# Battery_Monitoring_with_kill_Schematic.net
KiCad netlist of a schematic drawn in EAGLE
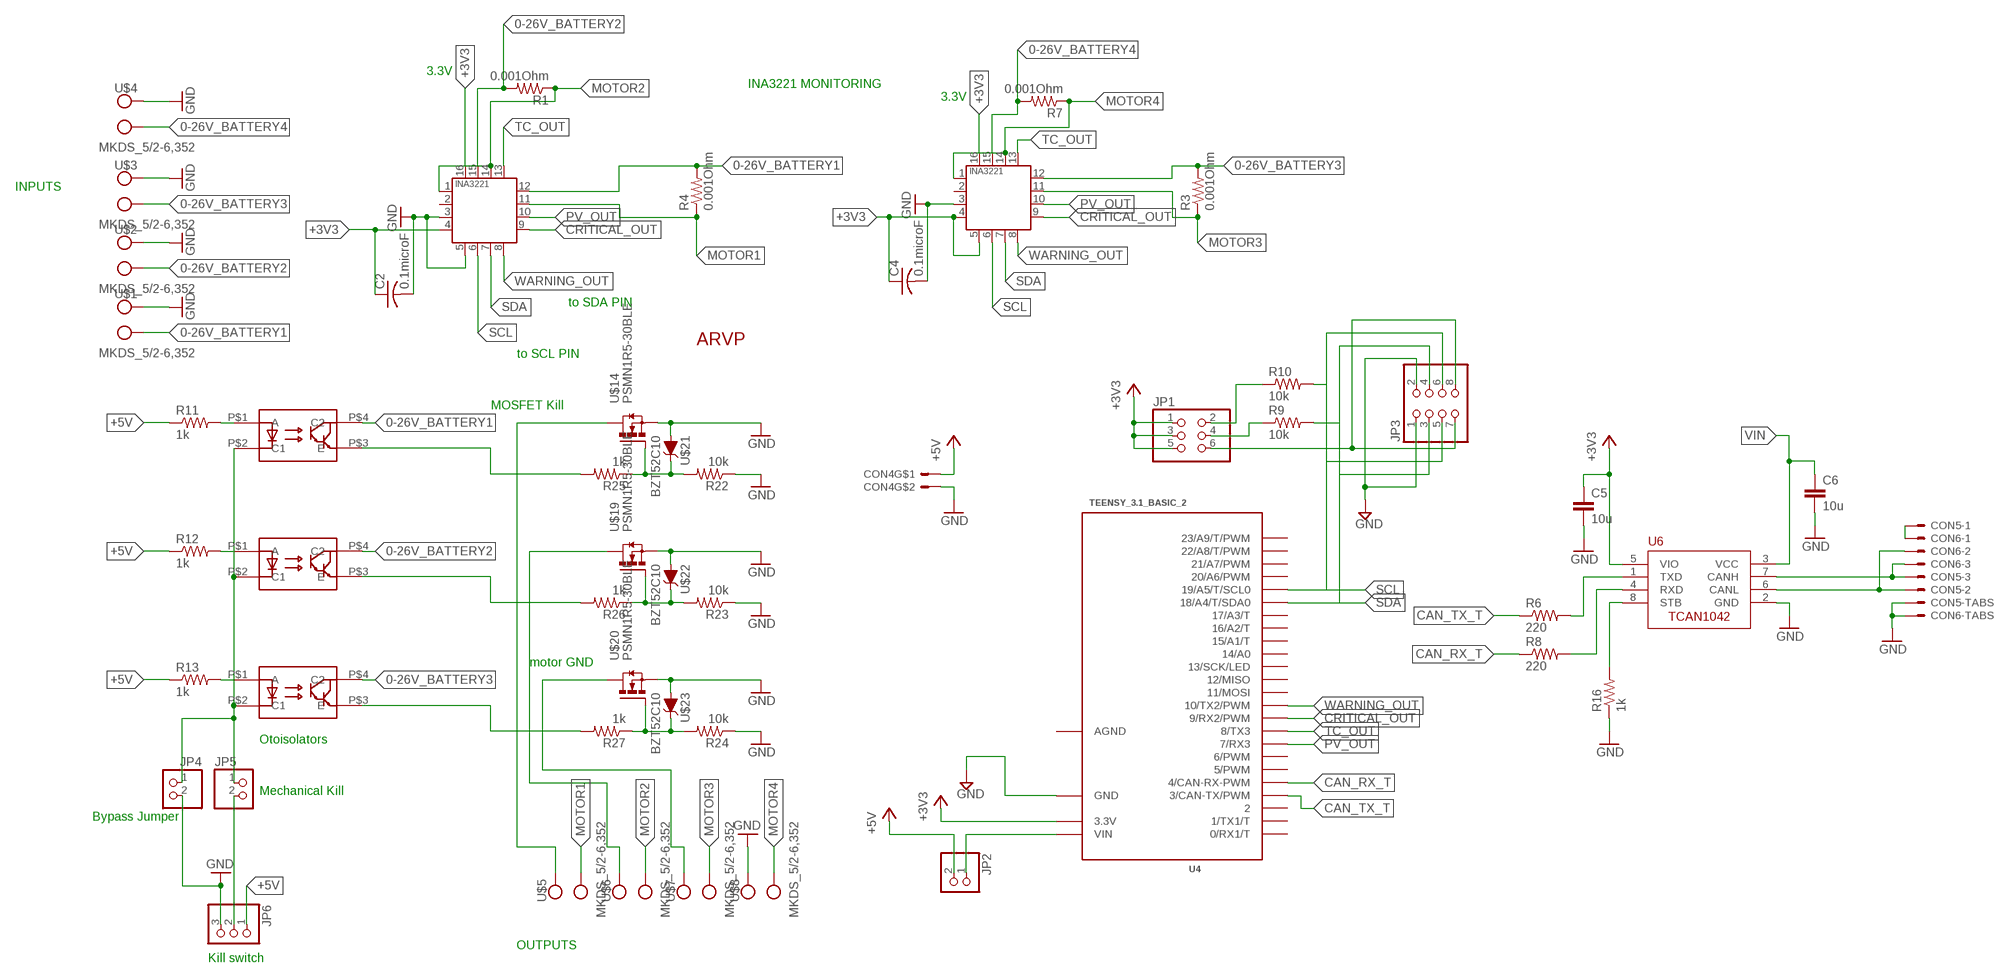
[diagram p0: schematic, sheet 1]

(export (version "E")
  (design (tool "Eeschema 10.0.6"))
  (components
    (comp (ref "C2")
      (value "0.1microF")
      (footprint "eagle-import:C2012")
      (libsource (lib "eagle-import") (part "C-USC2012"))
    )
    (comp (ref "C4")
      (value "0.1microF")
      (footprint "eagle-import:C2012")
      (libsource (lib "eagle-import") (part "C-USC2012"))
    )
    (comp (ref "C5")
      (value "10u")
      (footprint "eagle-import:C0805")
      (libsource (lib "eagle-import") (part "C-EUC0805"))
    )
    (comp (ref "C6")
      (value "10u")
      (footprint "eagle-import:C0805")
      (libsource (lib "eagle-import") (part "C-EUC0805"))
    )
    (comp (ref "CON4")
      (value "MOLEX_5566-2")
      (footprint "eagle-import:5566-2")
      (libsource (lib "eagle-import") (part "MOLEX_5566-2"))
    )
    (comp (ref "CON5")
      (value "S3B-PH-SM4-TB")
      (footprint "eagle-import:S3B-PH-SM4-TB")
      (libsource (lib "eagle-import") (part "S3B-PH-SM4-TB"))
    )
    (comp (ref "CON6")
      (value "S3B-PH-SM4-TB")
      (footprint "eagle-import:S3B-PH-SM4-TB")
      (libsource (lib "eagle-import") (part "S3B-PH-SM4-TB"))
    )
    (comp (ref "JP1")
      (value "PINHD-2X3")
      (footprint "eagle-import:2X03")
      (libsource (lib "eagle-import") (part "PINHD-2X3"))
    )
    (comp (ref "JP2")
      (value "PINHD-1X2")
      (footprint "eagle-import:1X02")
      (libsource (lib "eagle-import") (part "PINHD-1X2"))
    )
    (comp (ref "JP3")
      (value "PINHD-2X4")
      (footprint "eagle-import:2X04")
      (libsource (lib "eagle-import") (part "PINHD-2X4"))
    )
    (comp (ref "JP4")
      (value "PINHD-1X2")
      (footprint "eagle-import:1X02")
      (libsource (lib "eagle-import") (part "PINHD-1X2"))
    )
    (comp (ref "JP5")
      (value "PINHD-1X2")
      (footprint "eagle-import:1X02")
      (libsource (lib "eagle-import") (part "PINHD-1X2"))
    )
    (comp (ref "JP6")
      (value "PINHD-1X3")
      (footprint "eagle-import:1X03")
      (libsource (lib "eagle-import") (part "PINHD-1X3"))
    )
    (comp (ref "R1")
      (value "0.001Ohm")
      (footprint "eagle-import:3920")
      (libsource (lib "eagle-import") (part "HCS3920FT1L00"))
    )
    (comp (ref "R3")
      (value "0.001Ohm")
      (footprint "eagle-import:3920")
      (libsource (lib "eagle-import") (part "HCS3920FT1L00"))
    )
    (comp (ref "R4")
      (value "0.001Ohm")
      (footprint "eagle-import:3920")
      (libsource (lib "eagle-import") (part "HCS3920FT1L00"))
    )
    (comp (ref "R6")
      (value "220")
      (footprint "eagle-import:R0805")
      (libsource (lib "eagle-import") (part "rcl_334_R-US_R0805"))
    )
    (comp (ref "R7")
      (value "0.001Ohm")
      (footprint "eagle-import:3920")
      (libsource (lib "eagle-import") (part "HCS3920FT1L00"))
    )
    (comp (ref "R8")
      (value "220")
      (footprint "eagle-import:R0805")
      (libsource (lib "eagle-import") (part "rcl_334_R-US_R0805"))
    )
    (comp (ref "R9")
      (value "10k")
      (footprint "eagle-import:R1206")
      (libsource (lib "eagle-import") (part "rcl_334_R-US_R1206"))
    )
    (comp (ref "R10")
      (value "10k")
      (footprint "eagle-import:R1206")
      (libsource (lib "eagle-import") (part "rcl_334_R-US_R1206"))
    )
    (comp (ref "R11")
      (value "1k")
      (footprint "eagle-import:R0805")
      (libsource (lib "eagle-import") (part "R-US_R0805"))
    )
    (comp (ref "R12")
      (value "1k")
      (footprint "eagle-import:R0805")
      (libsource (lib "eagle-import") (part "R-US_R0805"))
    )
    (comp (ref "R13")
      (value "1k")
      (footprint "eagle-import:R0805")
      (libsource (lib "eagle-import") (part "R-US_R0805"))
    )
    (comp (ref "R16")
      (value "1k")
      (footprint "eagle-import:R0805")
      (libsource (lib "eagle-import") (part "rcl_334_R-US_R0805"))
    )
    (comp (ref "R22")
      (value "10k")
      (footprint "eagle-import:M1206")
      (libsource (lib "eagle-import") (part "R-US_M1206"))
    )
    (comp (ref "R23")
      (value "10k")
      (footprint "eagle-import:M1206")
      (libsource (lib "eagle-import") (part "R-US_M1206"))
    )
    (comp (ref "R24")
      (value "10k")
      (footprint "eagle-import:M1206")
      (libsource (lib "eagle-import") (part "R-US_M1206"))
    )
    (comp (ref "R25")
      (value "1k")
      (footprint "eagle-import:M1206")
      (libsource (lib "eagle-import") (part "R-US_M1206"))
    )
    (comp (ref "R26")
      (value "1k")
      (footprint "eagle-import:M1206")
      (libsource (lib "eagle-import") (part "R-US_M1206"))
    )
    (comp (ref "R27")
      (value "1k")
      (footprint "eagle-import:M1206")
      (libsource (lib "eagle-import") (part "R-US_M1206"))
    )
    (comp (ref "U$1")
      (value "MKDS_5/2-6,352")
      (footprint "eagle-import:MKDS_5_2-6,35")
      (libsource (lib "eagle-import") (part "MKDS_5/2-6,352"))
    )
    (comp (ref "U$2")
      (value "MKDS_5/2-6,352")
      (footprint "eagle-import:MKDS_5_2-6,35")
      (libsource (lib "eagle-import") (part "MKDS_5/2-6,352"))
    )
    (comp (ref "U$3")
      (value "MKDS_5/2-6,352")
      (footprint "eagle-import:MKDS_5_2-6,35")
      (libsource (lib "eagle-import") (part "MKDS_5/2-6,352"))
    )
    (comp (ref "U$4")
      (value "MKDS_5/2-6,352")
      (footprint "eagle-import:MKDS_5_2-6,35")
      (libsource (lib "eagle-import") (part "MKDS_5/2-6,352"))
    )
    (comp (ref "U$5")
      (value "MKDS_5/2-6,352")
      (footprint "eagle-import:MKDS_5_2-6,35")
      (libsource (lib "eagle-import") (part "MKDS_5/2-6,352"))
    )
    (comp (ref "U$6")
      (value "MKDS_5/2-6,352")
      (footprint "eagle-import:MKDS_5_2-6,35")
      (libsource (lib "eagle-import") (part "MKDS_5/2-6,352"))
    )
    (comp (ref "U$7")
      (value "MKDS_5/2-6,352")
      (footprint "eagle-import:MKDS_5_2-6,35")
      (libsource (lib "eagle-import") (part "MKDS_5/2-6,352"))
    )
    (comp (ref "U$8")
      (value "MKDS_5/2-6,352")
      (footprint "eagle-import:MKDS_5_2-6,35")
      (libsource (lib "eagle-import") (part "MKDS_5/2-6,352"))
    )
    (comp (ref "U$10")
      (value "ARVP_LOGO")
      (footprint "eagle-import:ARVP")
      (libsource (lib "eagle-import") (part "ARVP_LOGO"))
    )
    (comp (ref "U$11")
      (value "TCLD1000CT")
      (footprint "eagle-import:SOP-4L")
      (fields (field (name "SPICEPREFIX") "E"))
      (libsource (lib "eagle-import") (part "TCLD1000CT"))
    )
    (comp (ref "U$12")
      (value "TCLD1000CT")
      (footprint "eagle-import:SOP-4L")
      (libsource (lib "eagle-import") (part "TCLD1000CT"))
    )
    (comp (ref "U$13")
      (value "TCLD1000CT")
      (footprint "eagle-import:SOP-4L")
      (libsource (lib "eagle-import") (part "TCLD1000CT"))
    )
    (comp (ref "U$14")
      (value "PSMN1R5-30BLE")
      (footprint "eagle-import:SOT404_D2PAK")
      (libsource (lib "eagle-import") (part "PSMN1R5-30BLE"))
    )
    (comp (ref "U$19")
      (value "PSMN1R5-30BLE")
      (footprint "eagle-import:SOT404_D2PAK")
      (libsource (lib "eagle-import") (part "PSMN1R5-30BLE"))
    )
    (comp (ref "U$20")
      (value "PSMN1R5-30BLE")
      (footprint "eagle-import:SOT404_D2PAK")
      (libsource (lib "eagle-import") (part "PSMN1R5-30BLE"))
    )
    (comp (ref "U$21")
      (value "BZT52C10")
      (footprint "eagle-import:SOD-123")
      (libsource (lib "eagle-import") (part "BZT52C10"))
    )
    (comp (ref "U$22")
      (value "BZT52C10")
      (footprint "eagle-import:SOD-123")
      (libsource (lib "eagle-import") (part "BZT52C10"))
    )
    (comp (ref "U$23")
      (value "BZT52C10")
      (footprint "eagle-import:SOD-123")
      (libsource (lib "eagle-import") (part "BZT52C10"))
    )
    (comp (ref "U1")
      (value "INA3221.")
      (footprint "eagle-import:HVQFN16_4X4")
      (libsource (lib "eagle-import") (part "INA3221."))
    )
    (comp (ref "U2")
      (value "INA3221.")
      (footprint "eagle-import:HVQFN16_4X4")
      (libsource (lib "eagle-import") (part "INA3221."))
    )
    (comp (ref "U4")
      (value "TEENSY_3.1_BASIC_2")
      (footprint "eagle-import:TEENSY_3.1_BASIC_2")
      (libsource (lib "eagle-import") (part "TEENSY_3.1_BASIC_2"))
    )
    (comp (ref "U6")
      (value "TCAN1042HVDR")
      (footprint "eagle-import:SO-8")
      (libsource (lib "eagle-import") (part "TCAN1042HVDR"))
    )
  )
  (nets
    (net (code "1") (name "+3V3") (class "Default")
      (node (ref "C2") (pin "1") (pinfunction "1_1") (pintype "passive"))
      (node (ref "C4") (pin "1") (pinfunction "1_1") (pintype "passive"))
      (node (ref "C5") (pin "1") (pinfunction "1_1") (pintype "passive"))
      (node (ref "JP1") (pin "1") (pinfunction "1_1") (pintype "passive"))
      (node (ref "JP1") (pin "3") (pinfunction "3_3") (pintype "passive"))
      (node (ref "JP1") (pin "5") (pinfunction "5_5") (pintype "passive"))
      (node (ref "U1") (pin "16") (pinfunction "VPU_16") (pintype "input"))
      (node (ref "U1") (pin "4") (pinfunction "VS_4") (pintype "power_in"))
      (node (ref "U2") (pin "16") (pinfunction "VPU_16") (pintype "input"))
      (node (ref "U2") (pin "4") (pinfunction "VS_4") (pintype "power_in"))
      (node (ref "U2") (pin "5") (pinfunction "A0_5") (pintype "input"))
      (node (ref "U4") (pin "3.3V") (pinfunction "3.3V_3.3V") (pintype "power_in"))
      (node (ref "U6") (pin "5") (pinfunction "VIO_5") (pintype "bidirectional"))
    )
    (net (code "2") (name "+5V") (class "Default")
      (node (ref "CON4") (pin "1") (pinfunction "S_1") (pintype "passive"))
      (node (ref "JP2") (pin "2") (pinfunction "2_2") (pintype "passive"))
      (node (ref "JP6") (pin "1") (pinfunction "1_1") (pintype "passive"))
      (node (ref "R11") (pin "1") (pinfunction "1_1") (pintype "passive"))
      (node (ref "R12") (pin "1") (pinfunction "1_1") (pintype "passive"))
      (node (ref "R13") (pin "1") (pinfunction "1_1") (pintype "passive"))
    )
    (net (code "3") (name "/AGND") (class "Default")
      (node (ref "U4") (pin "AGND") (pinfunction "AGND_AGND") (pintype "power_in"))
    )
    (net (code "4") (name "0-26V_BATTERY1") (class "Default")
      (node (ref "R4") (pin "P$2") (pinfunction "2_P$2") (pintype "passive"))
      (node (ref "U$1") (pin "1") (pinfunction "KL_1") (pintype "passive"))
      (node (ref "U$11") (pin "P$4") (pinfunction "C2_P$4") (pintype "bidirectional"))
      (node (ref "U1") (pin "12") (pinfunction "IN+1_12") (pintype "input"))
    )
    (net (code "5") (name "0-26V_BATTERY2") (class "Default")
      (node (ref "R1") (pin "P$2") (pinfunction "2_P$2") (pintype "passive"))
      (node (ref "U$12") (pin "P$4") (pinfunction "C2_P$4") (pintype "bidirectional"))
      (node (ref "U$2") (pin "1") (pinfunction "KL_1") (pintype "passive"))
      (node (ref "U1") (pin "15") (pinfunction "IN+2_15") (pintype "input"))
    )
    (net (code "6") (name "0-26V_BATTERY3") (class "Default")
      (node (ref "R3") (pin "P$2") (pinfunction "2_P$2") (pintype "passive"))
      (node (ref "U$13") (pin "P$4") (pinfunction "C2_P$4") (pintype "bidirectional"))
      (node (ref "U$3") (pin "1") (pinfunction "KL_1") (pintype "passive"))
      (node (ref "U2") (pin "12") (pinfunction "IN+1_12") (pintype "input"))
    )
    (net (code "7") (name "0-26V_BATTERY4") (class "Default")
      (node (ref "R7") (pin "P$2") (pinfunction "2_P$2") (pintype "passive"))
      (node (ref "U$4") (pin "1") (pinfunction "KL_1") (pintype "passive"))
      (node (ref "U2") (pin "15") (pinfunction "IN+2_15") (pintype "input"))
    )
    (net (code "8") (name "CAN_RX_T") (class "Default")
      (node (ref "R8") (pin "1") (pinfunction "1_1") (pintype "passive"))
      (node (ref "U4") (pin "4") (pinfunction "4/CAN-RX-PWM_4") (pintype "bidirectional"))
    )
    (net (code "9") (name "CAN_TX_T") (class "Default")
      (node (ref "R6") (pin "1") (pinfunction "1_1") (pintype "passive"))
      (node (ref "U4") (pin "3") (pinfunction "3/CAN-TX/PWM_3") (pintype "bidirectional"))
    )
    (net (code "10") (name "CRITICAL_OUT") (class "Default")
      (node (ref "U1") (pin "9") (pinfunction "CRITICAL_9") (pintype "output"))
      (node (ref "U2") (pin "9") (pinfunction "CRITICAL_9") (pintype "output"))
      (node (ref "U4") (pin "9") (pinfunction "9/RX2/PWM_9") (pintype "bidirectional"))
    )
    (net (code "11") (name "GND") (class "Default")
      (node (ref "C2") (pin "2") (pinfunction "2_2") (pintype "passive"))
      (node (ref "C4") (pin "2") (pinfunction "2_2") (pintype "passive"))
      (node (ref "C5") (pin "2") (pinfunction "2_2") (pintype "passive"))
      (node (ref "C6") (pin "2") (pinfunction "2_2") (pintype "passive"))
      (node (ref "CON4") (pin "2") (pinfunction "S_2") (pintype "passive"))
      (node (ref "CON5") (pin "P$4") (pinfunction "S_P$4") (pintype "passive"))
      (node (ref "CON5") (pin "P$5") (pinfunction "S_P$5") (pintype "passive"))
      (node (ref "CON6") (pin "P$4") (pinfunction "S_P$4") (pintype "passive"))
      (node (ref "CON6") (pin "P$5") (pinfunction "S_P$5") (pintype "passive"))
      (node (ref "JP3") (pin "1") (pinfunction "1_1") (pintype "passive"))
      (node (ref "JP3") (pin "2") (pinfunction "2_2") (pintype "passive"))
      (node (ref "JP4") (pin "2") (pinfunction "2_2") (pintype "passive"))
      (node (ref "JP6") (pin "3") (pinfunction "3_3") (pintype "passive"))
      (node (ref "R16") (pin "1") (pinfunction "1_1") (pintype "passive"))
      (node (ref "R22") (pin "1") (pinfunction "1_1") (pintype "passive"))
      (node (ref "R23") (pin "1") (pinfunction "1_1") (pintype "passive"))
      (node (ref "R24") (pin "1") (pinfunction "1_1") (pintype "passive"))
      (node (ref "U$1") (pin "2") (pinfunction "KL1_2") (pintype "passive"))
      (node (ref "U$14") (pin "3S") (pinfunction "S_3S") (pintype "passive"))
      (node (ref "U$19") (pin "3S") (pinfunction "S_3S") (pintype "passive"))
      (node (ref "U$2") (pin "2") (pinfunction "KL1_2") (pintype "passive"))
      (node (ref "U$20") (pin "3S") (pinfunction "S_3S") (pintype "passive"))
      (node (ref "U$21") (pin "P$2") (pinfunction "A_P$2") (pintype "passive"))
      (node (ref "U$22") (pin "P$2") (pinfunction "A_P$2") (pintype "passive"))
      (node (ref "U$23") (pin "P$2") (pinfunction "A_P$2") (pintype "passive"))
      (node (ref "U$3") (pin "2") (pinfunction "KL1_2") (pintype "passive"))
      (node (ref "U$4") (pin "2") (pinfunction "KL1_2") (pintype "passive"))
      (node (ref "U$8") (pin "2") (pinfunction "KL1_2") (pintype "passive"))
      (node (ref "U1") (pin "3") (pinfunction "GND_3") (pintype "power_in"))
      (node (ref "U1") (pin "5") (pinfunction "A0_5") (pintype "input"))
      (node (ref "U2") (pin "3") (pinfunction "GND_3") (pintype "power_in"))
      (node (ref "U4") (pin "GND") (pinfunction "GND_GND") (pintype "power_in"))
      (node (ref "U6") (pin "2") (pinfunction "GND_2") (pintype "bidirectional"))
    )
    (net (code "12") (name "MOTOR1") (class "Default")
      (node (ref "R4") (pin "P$1") (pinfunction "1_P$1") (pintype "passive"))
      (node (ref "U$5") (pin "1") (pinfunction "KL_1") (pintype "passive"))
      (node (ref "U1") (pin "11") (pinfunction "IN-1_11") (pintype "input"))
    )
    (net (code "13") (name "MOTOR2") (class "Default")
      (node (ref "R1") (pin "P$1") (pinfunction "1_P$1") (pintype "passive"))
      (node (ref "U$6") (pin "1") (pinfunction "KL_1") (pintype "passive"))
      (node (ref "U1") (pin "1") (pinfunction "IN-3_1") (pintype "input"))
      (node (ref "U1") (pin "14") (pinfunction "IN-2_14") (pintype "input"))
    )
    (net (code "14") (name "MOTOR3") (class "Default")
      (node (ref "R3") (pin "P$1") (pinfunction "1_P$1") (pintype "passive"))
      (node (ref "U$7") (pin "1") (pinfunction "KL_1") (pintype "passive"))
      (node (ref "U2") (pin "11") (pinfunction "IN-1_11") (pintype "input"))
    )
    (net (code "15") (name "MOTOR4") (class "Default")
      (node (ref "R7") (pin "P$1") (pinfunction "1_P$1") (pintype "passive"))
      (node (ref "U$8") (pin "1") (pinfunction "KL_1") (pintype "passive"))
      (node (ref "U2") (pin "1") (pinfunction "IN-3_1") (pintype "input"))
      (node (ref "U2") (pin "14") (pinfunction "IN-2_14") (pintype "input"))
    )
    (net (code "16") (name "Net-(CON5A-S)") (class "Default")
      (node (ref "CON5") (pin "P$1") (pinfunction "S_P$1") (pintype "passive"))
      (node (ref "CON6") (pin "P$1") (pinfunction "S_P$1") (pintype "passive"))
    )
    (net (code "17") (name "Net-(CON5B-S)") (class "Default")
      (node (ref "CON5") (pin "P$2") (pinfunction "S_P$2") (pintype "passive"))
      (node (ref "CON6") (pin "P$2") (pinfunction "S_P$2") (pintype "passive"))
      (node (ref "U6") (pin "6") (pinfunction "CANL_6") (pintype "bidirectional"))
    )
    (net (code "18") (name "Net-(CON5C-S)") (class "Default")
      (node (ref "CON5") (pin "P$3") (pinfunction "S_P$3") (pintype "passive"))
      (node (ref "CON6") (pin "P$3") (pinfunction "S_P$3") (pintype "passive"))
      (node (ref "U6") (pin "7") (pinfunction "CANH_7") (pintype "bidirectional"))
    )
    (net (code "19") (name "Net-(JP1-Pad2)") (class "Default")
      (node (ref "JP1") (pin "2") (pinfunction "2_2") (pintype "passive"))
      (node (ref "R10") (pin "1") (pinfunction "1_1") (pintype "passive"))
    )
    (net (code "20") (name "Net-(JP1-Pad4)") (class "Default")
      (node (ref "JP1") (pin "4") (pinfunction "4_4") (pintype "passive"))
      (node (ref "R9") (pin "1") (pinfunction "1_1") (pintype "passive"))
    )
    (net (code "21") (name "Net-(JP1-Pad6)") (class "Default")
      (node (ref "JP1") (pin "6") (pinfunction "6_6") (pintype "passive"))
      (node (ref "JP3") (pin "7") (pinfunction "7_7") (pintype "passive"))
      (node (ref "JP3") (pin "8") (pinfunction "8_8") (pintype "passive"))
    )
    (net (code "22") (name "Net-(JP5-Pad2)") (class "Default")
      (node (ref "JP5") (pin "2") (pinfunction "2_2") (pintype "passive"))
      (node (ref "JP6") (pin "2") (pinfunction "2_2") (pintype "passive"))
    )
    (net (code "23") (name "Net-(U$11-A)") (class "Default")
      (node (ref "R11") (pin "2") (pinfunction "2_2") (pintype "passive"))
      (node (ref "U$11") (pin "P$1") (pinfunction "A_P$1") (pintype "bidirectional"))
    )
    (net (code "24") (name "Net-(U$11-C1)") (class "Default")
      (node (ref "JP4") (pin "1") (pinfunction "1_1") (pintype "passive"))
      (node (ref "JP5") (pin "1") (pinfunction "1_1") (pintype "passive"))
      (node (ref "U$11") (pin "P$2") (pinfunction "C1_P$2") (pintype "bidirectional"))
      (node (ref "U$12") (pin "P$2") (pinfunction "C1_P$2") (pintype "bidirectional"))
      (node (ref "U$13") (pin "P$2") (pinfunction "C1_P$2") (pintype "bidirectional"))
    )
    (net (code "25") (name "Net-(U$11-E)") (class "Default")
      (node (ref "R25") (pin "2") (pinfunction "2_2") (pintype "passive"))
      (node (ref "U$11") (pin "P$3") (pinfunction "E_P$3") (pintype "bidirectional"))
    )
    (net (code "26") (name "Net-(U$12-A)") (class "Default")
      (node (ref "R12") (pin "2") (pinfunction "2_2") (pintype "passive"))
      (node (ref "U$12") (pin "P$1") (pinfunction "A_P$1") (pintype "bidirectional"))
    )
    (net (code "27") (name "Net-(U$12-E)") (class "Default")
      (node (ref "R26") (pin "2") (pinfunction "2_2") (pintype "passive"))
      (node (ref "U$12") (pin "P$3") (pinfunction "E_P$3") (pintype "bidirectional"))
    )
    (net (code "28") (name "Net-(U$13-A)") (class "Default")
      (node (ref "R13") (pin "2") (pinfunction "2_2") (pintype "passive"))
      (node (ref "U$13") (pin "P$1") (pinfunction "A_P$1") (pintype "bidirectional"))
    )
    (net (code "29") (name "Net-(U$13-E)") (class "Default")
      (node (ref "R27") (pin "2") (pinfunction "2_2") (pintype "passive"))
      (node (ref "U$13") (pin "P$3") (pinfunction "E_P$3") (pintype "bidirectional"))
    )
    (net (code "30") (name "Net-(U$14-D)") (class "Default")
      (node (ref "U$14") (pin "2D") (pinfunction "D_2D") (pintype "passive"))
      (node (ref "U$5") (pin "2") (pinfunction "KL1_2") (pintype "passive"))
    )
    (net (code "31") (name "Net-(U$14-G)") (class "Default")
      (node (ref "R22") (pin "2") (pinfunction "2_2") (pintype "passive"))
      (node (ref "R25") (pin "1") (pinfunction "1_1") (pintype "passive"))
      (node (ref "U$14") (pin "1G") (pinfunction "G_1G") (pintype "passive"))
      (node (ref "U$21") (pin "P$1") (pinfunction "C_P$1") (pintype "passive"))
    )
    (net (code "32") (name "Net-(U$19-D)") (class "Default")
      (node (ref "U$19") (pin "2D") (pinfunction "D_2D") (pintype "passive"))
      (node (ref "U$6") (pin "2") (pinfunction "KL1_2") (pintype "passive"))
    )
    (net (code "33") (name "Net-(U$19-G)") (class "Default")
      (node (ref "R23") (pin "2") (pinfunction "2_2") (pintype "passive"))
      (node (ref "R26") (pin "1") (pinfunction "1_1") (pintype "passive"))
      (node (ref "U$19") (pin "1G") (pinfunction "G_1G") (pintype "passive"))
      (node (ref "U$22") (pin "P$1") (pinfunction "C_P$1") (pintype "passive"))
    )
    (net (code "34") (name "Net-(U$20-D)") (class "Default")
      (node (ref "U$20") (pin "2D") (pinfunction "D_2D") (pintype "passive"))
      (node (ref "U$7") (pin "2") (pinfunction "KL1_2") (pintype "passive"))
    )
    (net (code "35") (name "Net-(U$20-G)") (class "Default")
      (node (ref "R24") (pin "2") (pinfunction "2_2") (pintype "passive"))
      (node (ref "R27") (pin "1") (pinfunction "1_1") (pintype "passive"))
      (node (ref "U$20") (pin "1G") (pinfunction "G_1G") (pintype "passive"))
      (node (ref "U$23") (pin "P$1") (pinfunction "C_P$1") (pintype "passive"))
    )
    (net (code "36") (name "Net-(U6-RXD)") (class "Default")
      (node (ref "R8") (pin "2") (pinfunction "2_2") (pintype "passive"))
      (node (ref "U6") (pin "4") (pinfunction "RXD_4") (pintype "bidirectional"))
    )
    (net (code "37") (name "Net-(U6-STB)") (class "Default")
      (node (ref "R16") (pin "2") (pinfunction "2_2") (pintype "passive"))
      (node (ref "U6") (pin "8") (pinfunction "STB_8") (pintype "bidirectional"))
    )
    (net (code "38") (name "Net-(U6-TXD)") (class "Default")
      (node (ref "R6") (pin "2") (pinfunction "2_2") (pintype "passive"))
      (node (ref "U6") (pin "1") (pinfunction "TXD_1") (pintype "bidirectional"))
    )
    (net (code "39") (name "PV_OUT") (class "Default")
      (node (ref "U1") (pin "10") (pinfunction "PV_10") (pintype "output"))
      (node (ref "U2") (pin "10") (pinfunction "PV_10") (pintype "output"))
      (node (ref "U4") (pin "7") (pinfunction "7/RX3_7") (pintype "bidirectional"))
    )
    (net (code "40") (name "SCL") (class "Default")
      (node (ref "JP3") (pin "5") (pinfunction "5_5") (pintype "passive"))
      (node (ref "JP3") (pin "6") (pinfunction "6_6") (pintype "passive"))
      (node (ref "R10") (pin "2") (pinfunction "2_2") (pintype "passive"))
      (node (ref "U1") (pin "6") (pinfunction "SCL_6") (pintype "input"))
      (node (ref "U2") (pin "6") (pinfunction "SCL_6") (pintype "input"))
      (node (ref "U4") (pin "19/A5") (pinfunction "19/A5/T/SCL0_19/A5") (pintype "bidirectional"))
    )
    (net (code "41") (name "SDA") (class "Default")
      (node (ref "JP3") (pin "3") (pinfunction "3_3") (pintype "passive"))
      (node (ref "JP3") (pin "4") (pinfunction "4_4") (pintype "passive"))
      (node (ref "R9") (pin "2") (pinfunction "2_2") (pintype "passive"))
      (node (ref "U1") (pin "7") (pinfunction "SDA_7") (pintype "bidirectional"))
      (node (ref "U2") (pin "7") (pinfunction "SDA_7") (pintype "bidirectional"))
      (node (ref "U4") (pin "18/A4") (pinfunction "18/A4/T/SDA0_18/A4") (pintype "bidirectional"))
    )
    (net (code "42") (name "TC_OUT") (class "Default")
      (node (ref "U1") (pin "13") (pinfunction "TC_13") (pintype "output"))
      (node (ref "U2") (pin "13") (pinfunction "TC_13") (pintype "output"))
      (node (ref "U4") (pin "8") (pinfunction "8/TX3_8") (pintype "bidirectional"))
    )
    (net (code "43") (name "VIN") (class "Default")
      (node (ref "C6") (pin "1") (pinfunction "1_1") (pintype "passive"))
      (node (ref "JP2") (pin "1") (pinfunction "1_1") (pintype "passive"))
      (node (ref "U4") (pin "VIN") (pinfunction "VIN_VIN") (pintype "power_in"))
      (node (ref "U6") (pin "3") (pinfunction "VCC_3") (pintype "bidirectional"))
    )
    (net (code "44") (name "WARNING_OUT") (class "Default")
      (node (ref "U1") (pin "8") (pinfunction "WARNING_8") (pintype "output"))
      (node (ref "U2") (pin "8") (pinfunction "WARNING_8") (pintype "output"))
      (node (ref "U4") (pin "10") (pinfunction "10/TX2/PWM_10") (pintype "bidirectional"))
    )
    (net (code "45") (name "unconnected-(U1-IN+3-Pad2)") (class "Default")
      (node (ref "U1") (pin "2") (pinfunction "IN+3_2") (pintype "input"))
    )
    (net (code "46") (name "unconnected-(U2-IN+3-Pad2)") (class "Default")
      (node (ref "U2") (pin "2") (pinfunction "IN+3_2") (pintype "input"))
    )
    (net (code "47") (name "unconnected-(U4-0{slash}RX1{slash}T-Pad0)") (class "Default")
      (node (ref "U4") (pin "0") (pinfunction "0/RX1/T_0") (pintype "bidirectional"))
    )
    (net (code "48") (name "unconnected-(U4-1{slash}TX1{slash}T-Pad1)") (class "Default")
      (node (ref "U4") (pin "1") (pinfunction "1/TX1/T_1") (pintype "bidirectional"))
    )
    (net (code "49") (name "unconnected-(U4-5{slash}PWM-Pad5)") (class "Default")
      (node (ref "U4") (pin "5") (pinfunction "5/PWM_5") (pintype "bidirectional"))
    )
    (net (code "50") (name "unconnected-(U4-6{slash}PWM-Pad6)") (class "Default")
      (node (ref "U4") (pin "6") (pinfunction "6/PWM_6") (pintype "bidirectional"))
    )
    (net (code "51") (name "unconnected-(U4-11{slash}MOSI-Pad11)") (class "Default")
      (node (ref "U4") (pin "11") (pinfunction "11/MOSI_11") (pintype "bidirectional"))
    )
    (net (code "52") (name "unconnected-(U4-12{slash}MISO-Pad12)") (class "Default")
      (node (ref "U4") (pin "12") (pinfunction "12/MISO_12") (pintype "bidirectional"))
    )
    (net (code "53") (name "unconnected-(U4-13{slash}SCK{slash}LED-Pad13)") (class "Default")
      (node (ref "U4") (pin "13") (pinfunction "13/SCK/LED_13") (pintype "bidirectional"))
    )
    (net (code "54") (name "unconnected-(U4-15{slash}A1{slash}T-Pad15{slash}A1)") (class "Default")
      (node (ref "U4") (pin "15/A1") (pinfunction "15/A1/T_15/A1") (pintype "bidirectional"))
    )
    (net (code "55") (name "unconnected-(U4-16{slash}A2{slash}T-Pad16{slash}A2)") (class "Default")
      (node (ref "U4") (pin "16/A2") (pinfunction "16/A2/T_16/A2") (pintype "bidirectional"))
    )
    (net (code "56") (name "unconnected-(U4-17{slash}A3{slash}T-Pad17{slash}A3)") (class "Default")
      (node (ref "U4") (pin "17/A3") (pinfunction "17/A3/T_17/A3") (pintype "bidirectional"))
    )
    (net (code "57") (name "unconnected-(U4-20{slash}A6{slash}PWM-Pad20{slash}A6)") (class "Default")
      (node (ref "U4") (pin "20/A6") (pinfunction "20/A6/PWM_20/A6") (pintype "bidirectional"))
    )
    (net (code "58") (name "unconnected-(U4-21{slash}A7{slash}PWM-Pad21{slash}A7)") (class "Default")
      (node (ref "U4") (pin "21/A7") (pinfunction "21/A7/PWM_21/A7") (pintype "bidirectional"))
    )
    (net (code "59") (name "unconnected-(U4-22{slash}A8{slash}T{slash}PWM-Pad22{slash}A8)") (class "Default")
      (node (ref "U4") (pin "22/A8") (pinfunction "22/A8/T/PWM_22/A8") (pintype "bidirectional"))
    )
    (net (code "60") (name "unconnected-(U4-23{slash}A9{slash}T{slash}PWM-Pad23{slash}A9)") (class "Default")
      (node (ref "U4") (pin "23/A9") (pinfunction "23/A9/T/PWM_23/A9") (pintype "bidirectional"))
    )
    (net (code "61") (name "unconnected-(U4-Pad2)") (class "Default")
      (node (ref "U4") (pin "2") (pinfunction "2_2") (pintype "bidirectional"))
    )
    (net (code "62") (name "unconnected-(U4-Pad14{slash}A0)") (class "Default")
      (node (ref "U4") (pin "14/A0") (pinfunction "14/A0_14/A0") (pintype "bidirectional"))
    )
  )
)
